# MIDI.net
KiCad netlist of a schematic drawn in Altium Designer
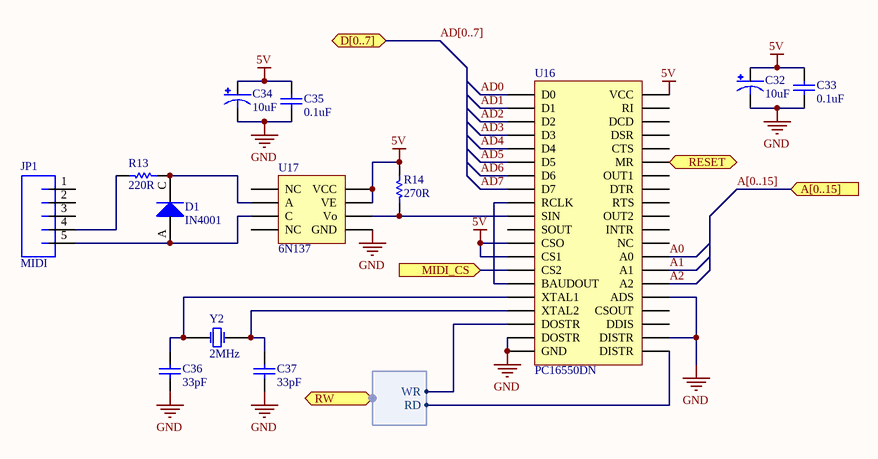
[diagram p0: MIDI.SchDoc]

(export (version "E")
  (design (tool "Eeschema 10.0.6"))
  (components
    (comp (ref "C32")
      (value "10uF")
      (footprint "CPOL-RADIAL")
      (libsource (lib "Components") (part "PolarizedCap"))
    )
    (comp (ref "C33") (value "0.1uF") (footprint "CAP-PTH") (libsource (lib "Components") (part "Cap")))
    (comp (ref "C34")
      (value "10uF")
      (footprint "CPOL-RADIAL")
      (libsource (lib "Components") (part "PolarizedCap"))
    )
    (comp (ref "C35") (value "0.1uF") (footprint "CAP-PTH") (libsource (lib "Components") (part "Cap")))
    (comp (ref "C36") (value "33pF") (footprint "CAP-PTH") (libsource (lib "Components") (part "Cap")))
    (comp (ref "C37") (value "33pF") (footprint "CAP-PTH") (libsource (lib "Components") (part "Cap")))
    (comp (ref "D1")
      (value "IN4001")
      (footprint "DIODE-1N4001")
      (libsource (lib "Components") (part "IN4001"))
    )
    (comp (ref "JP1") (value "MIDI") (footprint "DIN_5_FEMALE") (libsource (lib "Components") (part "MIDI")))
    (comp (ref "R13") (value "220R") (footprint "RESISTOR") (libsource (lib "Components") (part "Resistor")))
    (comp (ref "R14") (value "270R") (footprint "RESISTOR") (libsource (lib "Components") (part "Resistor")))
    (comp (ref "U16")
      (value "PC16550DN")
      (footprint "PDIP-40")
      (fields (field (name "MANUFACTURER") "Texas Instruments"))
      (libsource (lib "ICs") (part "PC16550DN"))
    )
    (comp (ref "U17") (value "6N137") (footprint "PDIP-8") (libsource (lib "ICs") (part "6N137")))
    (comp (ref "Y2") (value "2MHz") (footprint "CRYSTAL_PTH") (libsource (lib "Components") (part "Crystal")))
  )
  (nets
    (net (code "15") (name "/A0") (class "Default")
      (node (ref "U16") (pin "28") (pinfunction "A0_28") (pintype "passive"))
    )
    (net (code "16") (name "/A1") (class "Default")
      (node (ref "U16") (pin "27") (pinfunction "A1_27") (pintype "passive"))
    )
    (net (code "17") (name "/A2") (class "Default")
      (node (ref "U16") (pin "26") (pinfunction "A2_26") (pintype "passive"))
    )
    (net (code "18") (name "/AD0") (class "Default")
      (node (ref "U16") (pin "1") (pinfunction "D0_1") (pintype "passive"))
    )
    (net (code "19") (name "/AD1") (class "Default")
      (node (ref "U16") (pin "2") (pinfunction "D1_2") (pintype "passive"))
    )
    (net (code "20") (name "/AD2") (class "Default")
      (node (ref "U16") (pin "3") (pinfunction "D2_3") (pintype "passive"))
    )
    (net (code "21") (name "/AD3") (class "Default")
      (node (ref "U16") (pin "4") (pinfunction "D3_4") (pintype "passive"))
    )
    (net (code "22") (name "/AD4") (class "Default")
      (node (ref "U16") (pin "5") (pinfunction "D4_5") (pintype "passive"))
    )
    (net (code "23") (name "/AD5") (class "Default")
      (node (ref "U16") (pin "6") (pinfunction "D5_6") (pintype "passive"))
    )
    (net (code "24") (name "/AD6") (class "Default")
      (node (ref "U16") (pin "7") (pinfunction "D6_7") (pintype "passive"))
    )
    (net (code "25") (name "/AD7") (class "Default")
      (node (ref "U16") (pin "8") (pinfunction "D7_8") (pintype "passive"))
    )
    (net (code "28") (name "/MIDI_CS") (class "Default")
      (node (ref "U16") (pin "14") (pinfunction "CS2_14") (pintype "passive"))
    )
    (net (code "29") (name "/RD") (class "Default")
      (node (ref "U16") (pin "21") (pinfunction "DISTR_21") (pintype "passive"))
    )
    (net (code "30") (name "/RESET") (class "Default")
      (node (ref "U16") (pin "35") (pinfunction "MR_35") (pintype "passive"))
    )
    (net (code "31") (name "/WR") (class "Default")
      (node (ref "U16") (pin "18") (pinfunction "DOSTR_18") (pintype "passive"))
    )
    (net (code "33") (name "5V") (class "Default")
      (node (ref "C32") (pin "1") (pinfunction "+_1") (pintype "passive"))
      (node (ref "C33") (pin "1") (pinfunction "1_1") (pintype "passive"))
      (node (ref "C34") (pin "1") (pinfunction "+_1") (pintype "passive"))
      (node (ref "C35") (pin "1") (pinfunction "1_1") (pintype "passive"))
      (node (ref "R14") (pin "2") (pinfunction "2_2") (pintype "passive"))
      (node (ref "U16") (pin "12") (pinfunction "CSO_12") (pintype "passive"))
      (node (ref "U16") (pin "13") (pinfunction "CS1_13") (pintype "passive"))
      (node (ref "U16") (pin "40") (pinfunction "VCC_40") (pintype "passive"))
      (node (ref "U17") (pin "7") (pinfunction "VE_7") (pintype "passive"))
      (node (ref "U17") (pin "8") (pinfunction "VCC_8") (pintype "passive"))
    )
    (net (code "34") (name "GND") (class "Default")
      (node (ref "C32") (pin "2") (pinfunction "-_2") (pintype "passive"))
      (node (ref "C33") (pin "2") (pinfunction "2_2") (pintype "passive"))
      (node (ref "C34") (pin "2") (pinfunction "-_2") (pintype "passive"))
      (node (ref "C35") (pin "2") (pinfunction "2_2") (pintype "passive"))
      (node (ref "C36") (pin "2") (pinfunction "2_2") (pintype "passive"))
      (node (ref "C37") (pin "2") (pinfunction "2_2") (pintype "passive"))
      (node (ref "U16") (pin "19") (pinfunction "DOSTR_19") (pintype "passive"))
      (node (ref "U16") (pin "20") (pinfunction "GND_20") (pintype "passive"))
      (node (ref "U16") (pin "22") (pinfunction "DISTR_22") (pintype "passive"))
      (node (ref "U16") (pin "25") (pinfunction "ADS_25") (pintype "passive"))
      (node (ref "U17") (pin "5") (pinfunction "GND_5") (pintype "passive"))
    )
    (net (code "35") (name "Net-(D1-K)") (class "Default")
      (node (ref "D1") (pin "C") (pinfunction "K_C") (pintype "passive"))
      (node (ref "R13") (pin "2") (pinfunction "2_2") (pintype "passive"))
      (node (ref "U17") (pin "2") (pinfunction "A_2") (pintype "passive"))
    )
    (net (code "36") (name "Net-(JP1-Pad4)") (class "Default")
      (node (ref "JP1") (pin "4") (pinfunction "4_4") (pintype "passive"))
      (node (ref "R13") (pin "1") (pinfunction "1_1") (pintype "passive"))
    )
    (net (code "37") (name "Net-(U16-BAUDOUT)") (class "Default")
      (node (ref "U16") (pin "15") (pinfunction "BAUDOUT_15") (pintype "passive"))
      (node (ref "U16") (pin "9") (pinfunction "RCLK_9") (pintype "passive"))
    )
    (net (code "38") (name "Net-(U16-SIN)") (class "Default")
      (node (ref "R14") (pin "1") (pinfunction "1_1") (pintype "passive"))
      (node (ref "U16") (pin "10") (pinfunction "SIN_10") (pintype "passive"))
      (node (ref "U17") (pin "6") (pinfunction "Vo_6") (pintype "passive"))
    )
    (net (code "39") (name "Net-(U16-XTAL1)") (class "Default")
      (node (ref "C36") (pin "1") (pinfunction "1_1") (pintype "passive"))
      (node (ref "U16") (pin "16") (pinfunction "XTAL1_16") (pintype "passive"))
      (node (ref "Y2") (pin "1") (pinfunction "X1_1") (pintype "passive"))
    )
    (net (code "40") (name "Net-(U16-XTAL2)") (class "Default")
      (node (ref "C37") (pin "1") (pinfunction "1_1") (pintype "passive"))
      (node (ref "U16") (pin "17") (pinfunction "XTAL2_17") (pintype "passive"))
      (node (ref "Y2") (pin "2") (pinfunction "X2_2") (pintype "passive"))
    )
    (net (code "41") (name "Net-(U17-C)") (class "Default")
      (node (ref "D1") (pin "A") (pinfunction "A_A") (pintype "passive"))
      (node (ref "JP1") (pin "5") (pinfunction "5_5") (pintype "passive"))
      (node (ref "U17") (pin "3") (pinfunction "C_3") (pintype "passive"))
    )
    (net (code "42") (name "unconnected-(JP1-Pad1)") (class "Default")
      (node (ref "JP1") (pin "1") (pinfunction "1_1") (pintype "passive"))
    )
    (net (code "43") (name "unconnected-(JP1-Pad2)") (class "Default")
      (node (ref "JP1") (pin "2") (pinfunction "2_2") (pintype "passive"))
    )
    (net (code "44") (name "unconnected-(JP1-Pad3)") (class "Default")
      (node (ref "JP1") (pin "3") (pinfunction "3_3") (pintype "passive"))
    )
    (net (code "45") (name "unconnected-(U16-CSOUT-Pad24)") (class "Default")
      (node (ref "U16") (pin "24") (pinfunction "CSOUT_24") (pintype "passive"))
    )
    (net (code "46") (name "unconnected-(U16-CTS-Pad36)") (class "Default")
      (node (ref "U16") (pin "36") (pinfunction "CTS_36") (pintype "passive"))
    )
    (net (code "47") (name "unconnected-(U16-DCD-Pad38)") (class "Default")
      (node (ref "U16") (pin "38") (pinfunction "DCD_38") (pintype "passive"))
    )
    (net (code "48") (name "unconnected-(U16-DDIS-Pad23)") (class "Default")
      (node (ref "U16") (pin "23") (pinfunction "DDIS_23") (pintype "passive"))
    )
    (net (code "49") (name "unconnected-(U16-DSR-Pad37)") (class "Default")
      (node (ref "U16") (pin "37") (pinfunction "DSR_37") (pintype "passive"))
    )
    (net (code "50") (name "unconnected-(U16-DTR-Pad33)") (class "Default")
      (node (ref "U16") (pin "33") (pinfunction "DTR_33") (pintype "passive"))
    )
    (net (code "51") (name "unconnected-(U16-INTR-Pad30)") (class "Default")
      (node (ref "U16") (pin "30") (pinfunction "INTR_30") (pintype "passive"))
    )
    (net (code "52") (name "unconnected-(U16-NC-Pad29)") (class "Default")
      (node (ref "U16") (pin "29") (pinfunction "NC_29") (pintype "passive"))
    )
    (net (code "53") (name "unconnected-(U16-OUT1-Pad34)") (class "Default")
      (node (ref "U16") (pin "34") (pinfunction "OUT1_34") (pintype "passive"))
    )
    (net (code "54") (name "unconnected-(U16-OUT2-Pad31)") (class "Default")
      (node (ref "U16") (pin "31") (pinfunction "OUT2_31") (pintype "passive"))
    )
    (net (code "55") (name "unconnected-(U16-RI-Pad39)") (class "Default")
      (node (ref "U16") (pin "39") (pinfunction "RI_39") (pintype "passive"))
    )
    (net (code "56") (name "unconnected-(U16-RTS-Pad32)") (class "Default")
      (node (ref "U16") (pin "32") (pinfunction "RTS_32") (pintype "passive"))
    )
    (net (code "57") (name "unconnected-(U16-SOUT-Pad11)") (class "Default")
      (node (ref "U16") (pin "11") (pinfunction "SOUT_11") (pintype "passive"))
    )
    (net (code "58") (name "unconnected-(U17-NC-Pad1)") (class "Default")
      (node (ref "U17") (pin "1") (pinfunction "NC_1") (pintype "passive"))
    )
    (net (code "59") (name "unconnected-(U17-NC-Pad4)") (class "Default")
      (node (ref "U17") (pin "4") (pinfunction "NC_4") (pintype "passive"))
    )
  )
)
